# layer1v2.net
KiCad netlist of a schematic drawn in EAGLE
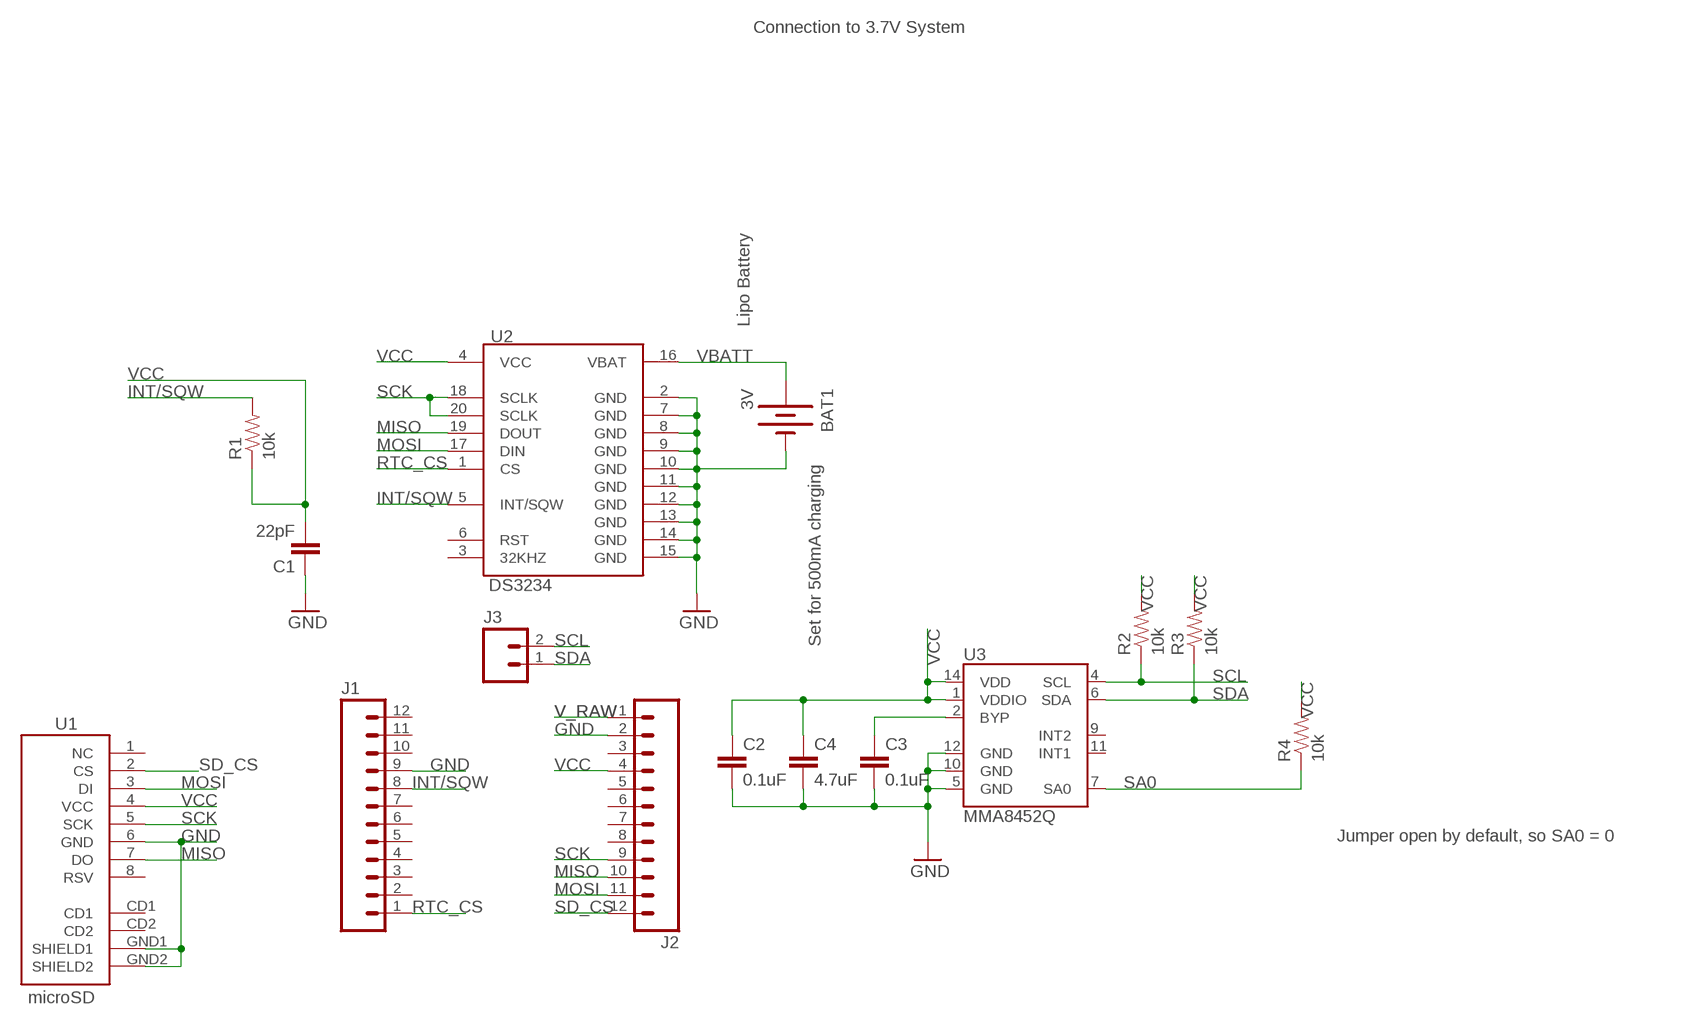
[diagram p0: schematic, sheet 1]

(export (version "E")
  (design (tool "Eeschema 10.0.6"))
  (components
    (comp (ref "BAT1")
      (value "3V")
      (footprint "eagle-import:BATTCON_12MM_CURVED")
      (libsource (lib "eagle-import") (part "BATTERY"))
    )
    (comp (ref "C1")
      (value "22pF")
      (footprint "eagle-import:0402-CAP")
      (libsource (lib "eagle-import") (part "CAP0402-CAP"))
    )
    (comp (ref "C2")
      (value "0.1uF")
      (footprint "eagle-import:0402-CAP")
      (libsource (lib "eagle-import") (part "CAP0402-CAP"))
    )
    (comp (ref "C3")
      (value "0.1uF")
      (footprint "eagle-import:0402-CAP")
      (libsource (lib "eagle-import") (part "CAP0402-CAP"))
    )
    (comp (ref "C4")
      (value "4.7uF")
      (footprint "eagle-import:0402-CAP")
      (libsource (lib "eagle-import") (part "CAP0402-CAP"))
    )
    (comp (ref "J1")
      (value "M12PTH")
      (footprint "eagle-import:1X12")
      (libsource (lib "eagle-import") (part "M12PTH"))
    )
    (comp (ref "J2")
      (value "M12PTH")
      (footprint "eagle-import:1X12")
      (libsource (lib "eagle-import") (part "M12PTH"))
    )
    (comp (ref "J3")
      (value "M02LOCK")
      (footprint "eagle-import:1X02_LOCK")
      (libsource (lib "eagle-import") (part "M02LOCK"))
    )
    (comp (ref "R1")
      (value "10k")
      (footprint "eagle-import:0402-RES")
      (libsource (lib "eagle-import") (part "RESISTOR0402-RES"))
    )
    (comp (ref "R2")
      (value "10k")
      (footprint "eagle-import:0402-RES")
      (libsource (lib "eagle-import") (part "RESISTOR0402-RES"))
    )
    (comp (ref "R3")
      (value "10k")
      (footprint "eagle-import:0402-RES")
      (libsource (lib "eagle-import") (part "RESISTOR0402-RES"))
    )
    (comp (ref "R4")
      (value "10k")
      (footprint "eagle-import:0402-RES")
      (libsource (lib "eagle-import") (part "RESISTOR0402-RES"))
    )
    (comp (ref "U1")
      (value "microSD")
      (footprint "eagle-import:MICRO-SD-SOCKET-PP")
      (libsource (lib "eagle-import") (part "USD-SOCKETSMD"))
    )
    (comp (ref "U2")
      (value "DS3234")
      (footprint "eagle-import:DS3234")
      (libsource (lib "eagle-import") (part "DS3234"))
    )
    (comp (ref "U3")
      (value "MMA8452Q")
      (footprint "eagle-import:QFN-16_0.5MM")
      (libsource (lib "eagle-import") (part "MMA8452Q"))
    )
  )
  (nets
    (net (code "1") (name "/INT{slash}SQW") (class "Default")
      (node (ref "J1") (pin "8") (pinfunction "8_8") (pintype "passive"))
      (node (ref "R1") (pin "2") (pinfunction "2_2") (pintype "passive"))
      (node (ref "U2") (pin "5") (pinfunction "INT/SQW_5") (pintype "bidirectional"))
    )
    (net (code "2") (name "/MISO") (class "Default")
      (node (ref "J2") (pin "10") (pinfunction "10_10") (pintype "passive"))
      (node (ref "U1") (pin "7") (pinfunction "DO_7") (pintype "bidirectional"))
      (node (ref "U2") (pin "19") (pinfunction "DOUT_19") (pintype "bidirectional"))
    )
    (net (code "3") (name "/MOSI") (class "Default")
      (node (ref "J2") (pin "11") (pinfunction "11_11") (pintype "passive"))
      (node (ref "U1") (pin "3") (pinfunction "DI_3") (pintype "bidirectional"))
      (node (ref "U2") (pin "17") (pinfunction "DIN_17") (pintype "bidirectional"))
    )
    (net (code "4") (name "/RTC_CS") (class "Default")
      (node (ref "J1") (pin "1") (pinfunction "1_1") (pintype "passive"))
      (node (ref "U2") (pin "1") (pinfunction "CS_1") (pintype "bidirectional"))
    )
    (net (code "5") (name "/SA0") (class "Default")
      (node (ref "R4") (pin "1") (pinfunction "1_1") (pintype "passive"))
      (node (ref "U3") (pin "7") (pinfunction "SA0_7") (pintype "bidirectional"))
    )
    (net (code "6") (name "/SCK") (class "Default")
      (node (ref "J2") (pin "9") (pinfunction "9_9") (pintype "passive"))
      (node (ref "U1") (pin "5") (pinfunction "SCK_5") (pintype "bidirectional"))
      (node (ref "U2") (pin "18") (pinfunction "SCLK_18") (pintype "bidirectional"))
      (node (ref "U2") (pin "20") (pinfunction "SCLK_20") (pintype "bidirectional"))
    )
    (net (code "7") (name "/SCL") (class "Default")
      (node (ref "J3") (pin "2") (pinfunction "2_2") (pintype "passive"))
      (node (ref "R2") (pin "1") (pinfunction "1_1") (pintype "passive"))
      (node (ref "U3") (pin "4") (pinfunction "SCL_4") (pintype "bidirectional"))
    )
    (net (code "8") (name "/SDA") (class "Default")
      (node (ref "J3") (pin "1") (pinfunction "1_1") (pintype "passive"))
      (node (ref "R3") (pin "1") (pinfunction "1_1") (pintype "passive"))
      (node (ref "U3") (pin "6") (pinfunction "SDA_6") (pintype "bidirectional"))
    )
    (net (code "9") (name "/SD_CS") (class "Default")
      (node (ref "J2") (pin "12") (pinfunction "12_12") (pintype "passive"))
      (node (ref "U1") (pin "2") (pinfunction "CS_2") (pintype "bidirectional"))
    )
    (net (code "10") (name "/VBATT") (class "Default")
      (node (ref "BAT1") (pin "PWR@1") (pinfunction "+_PWR@1") (pintype "power_in"))
      (node (ref "U2") (pin "16") (pinfunction "VBAT_16") (pintype "bidirectional"))
    )
    (net (code "11") (name "/VCC") (class "Default")
      (node (ref "C1") (pin "2") (pinfunction "2_2") (pintype "passive"))
      (node (ref "C2") (pin "1") (pinfunction "1_1") (pintype "passive"))
      (node (ref "C4") (pin "1") (pinfunction "1_1") (pintype "passive"))
      (node (ref "J2") (pin "4") (pinfunction "4_4") (pintype "passive"))
      (node (ref "R1") (pin "1") (pinfunction "1_1") (pintype "passive"))
      (node (ref "R2") (pin "2") (pinfunction "2_2") (pintype "passive"))
      (node (ref "R3") (pin "2") (pinfunction "2_2") (pintype "passive"))
      (node (ref "R4") (pin "2") (pinfunction "2_2") (pintype "passive"))
      (node (ref "U1") (pin "4") (pinfunction "VCC_4") (pintype "bidirectional"))
      (node (ref "U2") (pin "4") (pinfunction "VCC_4") (pintype "bidirectional"))
      (node (ref "U3") (pin "1") (pinfunction "VDDIO_1") (pintype "bidirectional"))
      (node (ref "U3") (pin "14") (pinfunction "VDD_14") (pintype "bidirectional"))
    )
    (net (code "12") (name "/V_RAW") (class "Default")
      (node (ref "J2") (pin "1") (pinfunction "1_1") (pintype "passive"))
    )
    (net (code "13") (name "GND") (class "Default")
      (node (ref "BAT1") (pin "GND") (pinfunction "-_GND") (pintype "power_in"))
      (node (ref "C1") (pin "1") (pinfunction "1_1") (pintype "passive"))
      (node (ref "C2") (pin "2") (pinfunction "2_2") (pintype "passive"))
      (node (ref "C3") (pin "2") (pinfunction "2_2") (pintype "passive"))
      (node (ref "C4") (pin "2") (pinfunction "2_2") (pintype "passive"))
      (node (ref "J1") (pin "9") (pinfunction "9_9") (pintype "passive"))
      (node (ref "J2") (pin "2") (pinfunction "2_2") (pintype "passive"))
      (node (ref "U1") (pin "6") (pinfunction "GND_6") (pintype "bidirectional"))
      (node (ref "U1") (pin "GND1") (pinfunction "SHIELD1_GND1") (pintype "bidirectional"))
      (node (ref "U1") (pin "GND2") (pinfunction "SHIELD2_GND2") (pintype "bidirectional"))
      (node (ref "U2") (pin "10") (pinfunction "GND_10") (pintype "bidirectional"))
      (node (ref "U2") (pin "11") (pinfunction "GND_11") (pintype "bidirectional"))
      (node (ref "U2") (pin "12") (pinfunction "GND_12") (pintype "bidirectional"))
      (node (ref "U2") (pin "13") (pinfunction "GND_13") (pintype "bidirectional"))
      (node (ref "U2") (pin "14") (pinfunction "GND_14") (pintype "bidirectional"))
      (node (ref "U2") (pin "15") (pinfunction "GND_15") (pintype "bidirectional"))
      (node (ref "U2") (pin "2") (pinfunction "GND_2") (pintype "bidirectional"))
      (node (ref "U2") (pin "7") (pinfunction "GND_7") (pintype "bidirectional"))
      (node (ref "U2") (pin "8") (pinfunction "GND_8") (pintype "bidirectional"))
      (node (ref "U2") (pin "9") (pinfunction "GND_9") (pintype "bidirectional"))
      (node (ref "U3") (pin "10") (pinfunction "GND_10") (pintype "bidirectional"))
      (node (ref "U3") (pin "12") (pinfunction "GND_12") (pintype "bidirectional"))
      (node (ref "U3") (pin "5") (pinfunction "GND_5") (pintype "bidirectional"))
    )
    (net (code "14") (name "Net-(U3-BYP)") (class "Default")
      (node (ref "C3") (pin "1") (pinfunction "1_1") (pintype "passive"))
      (node (ref "U3") (pin "2") (pinfunction "BYP_2") (pintype "bidirectional"))
    )
    (net (code "15") (name "unconnected-(J1-Pad2)") (class "Default")
      (node (ref "J1") (pin "2") (pinfunction "2_2") (pintype "passive"))
    )
    (net (code "16") (name "unconnected-(J1-Pad3)") (class "Default")
      (node (ref "J1") (pin "3") (pinfunction "3_3") (pintype "passive"))
    )
    (net (code "17") (name "unconnected-(J1-Pad4)") (class "Default")
      (node (ref "J1") (pin "4") (pinfunction "4_4") (pintype "passive"))
    )
    (net (code "18") (name "unconnected-(J1-Pad5)") (class "Default")
      (node (ref "J1") (pin "5") (pinfunction "5_5") (pintype "passive"))
    )
    (net (code "19") (name "unconnected-(J1-Pad6)") (class "Default")
      (node (ref "J1") (pin "6") (pinfunction "6_6") (pintype "passive"))
    )
    (net (code "20") (name "unconnected-(J1-Pad7)") (class "Default")
      (node (ref "J1") (pin "7") (pinfunction "7_7") (pintype "passive"))
    )
    (net (code "21") (name "unconnected-(J1-Pad10)") (class "Default")
      (node (ref "J1") (pin "10") (pinfunction "10_10") (pintype "passive"))
    )
    (net (code "22") (name "unconnected-(J1-Pad11)") (class "Default")
      (node (ref "J1") (pin "11") (pinfunction "11_11") (pintype "passive"))
    )
    (net (code "23") (name "unconnected-(J1-Pad12)") (class "Default")
      (node (ref "J1") (pin "12") (pinfunction "12_12") (pintype "passive"))
    )
    (net (code "24") (name "unconnected-(J2-Pad3)") (class "Default")
      (node (ref "J2") (pin "3") (pinfunction "3_3") (pintype "passive"))
    )
    (net (code "25") (name "unconnected-(J2-Pad5)") (class "Default")
      (node (ref "J2") (pin "5") (pinfunction "5_5") (pintype "passive"))
    )
    (net (code "26") (name "unconnected-(J2-Pad6)") (class "Default")
      (node (ref "J2") (pin "6") (pinfunction "6_6") (pintype "passive"))
    )
    (net (code "27") (name "unconnected-(J2-Pad7)") (class "Default")
      (node (ref "J2") (pin "7") (pinfunction "7_7") (pintype "passive"))
    )
    (net (code "28") (name "unconnected-(J2-Pad8)") (class "Default")
      (node (ref "J2") (pin "8") (pinfunction "8_8") (pintype "passive"))
    )
    (net (code "29") (name "unconnected-(U1-NC-Pad1)") (class "Default")
      (node (ref "U1") (pin "1") (pinfunction "NC_1") (pintype "bidirectional"))
    )
    (net (code "30") (name "unconnected-(U1-PadCD1)") (class "Default")
      (node (ref "U1") (pin "CD1") (pinfunction "CD1_CD1") (pintype "bidirectional"))
    )
    (net (code "31") (name "unconnected-(U1-PadCD2)") (class "Default")
      (node (ref "U1") (pin "CD2") (pinfunction "CD2_CD2") (pintype "bidirectional"))
    )
    (net (code "32") (name "unconnected-(U1-RSV-Pad8)") (class "Default")
      (node (ref "U1") (pin "8") (pinfunction "RSV_8") (pintype "bidirectional"))
    )
    (net (code "33") (name "unconnected-(U2-32KHZ-Pad3)") (class "Default")
      (node (ref "U2") (pin "3") (pinfunction "32KHZ_3") (pintype "bidirectional"))
    )
    (net (code "34") (name "unconnected-(U2-RST-Pad6)") (class "Default")
      (node (ref "U2") (pin "6") (pinfunction "RST_6") (pintype "bidirectional"))
    )
    (net (code "35") (name "unconnected-(U3-INT1-Pad11)") (class "Default")
      (node (ref "U3") (pin "11") (pinfunction "INT1_11") (pintype "bidirectional"))
    )
    (net (code "36") (name "unconnected-(U3-INT2-Pad9)") (class "Default")
      (node (ref "U3") (pin "9") (pinfunction "INT2_9") (pintype "bidirectional"))
    )
  )
)
